# 1_Level_Convertor.net
KiCad netlist of a schematic drawn in EAGLE
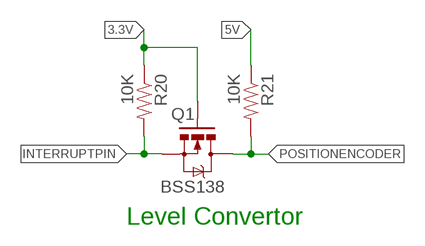
[diagram p0: schematic, sheet 1]

(export (version "E")
  (design (tool "Eeschema 10.0.6"))
  (components
    (comp (ref "Q1")
      (value "BSS138")
      (footprint "eagle-import:SOT23-3")
      (libsource (lib "eagle-import") (part "MOSFET-NCHANNELSMD"))
    )
    (comp (ref "R20")
      (value "10K")
      (footprint "eagle-import:1206")
      (libsource (lib "eagle-import") (part "RESISTOR1206"))
    )
    (comp (ref "R21")
      (value "10K")
      (footprint "eagle-import:1206")
      (libsource (lib "eagle-import") (part "RESISTOR1206"))
    )
  )
  (nets
    (net (code "1") (name "3.3V") (class "Default")
      (node (ref "Q1") (pin "1") (pinfunction "G_1") (pintype "passive"))
      (node (ref "R20") (pin "1") (pinfunction "1_1") (pintype "passive"))
    )
    (net (code "2") (name "5V") (class "Default")
      (node (ref "R21") (pin "1") (pinfunction "1_1") (pintype "passive"))
    )
    (net (code "3") (name "INTERRUPTPIN") (class "Default")
      (node (ref "Q1") (pin "2") (pinfunction "S_2") (pintype "passive"))
      (node (ref "R20") (pin "2") (pinfunction "2_2") (pintype "passive"))
    )
    (net (code "4") (name "POSITIONENCODER") (class "Default")
      (node (ref "Q1") (pin "3") (pinfunction "D_3") (pintype "passive"))
      (node (ref "R21") (pin "2") (pinfunction "2_2") (pintype "passive"))
    )
  )
)
